# LISC_TopLevel.net
KiCad netlist of a schematic drawn in Altium Designer
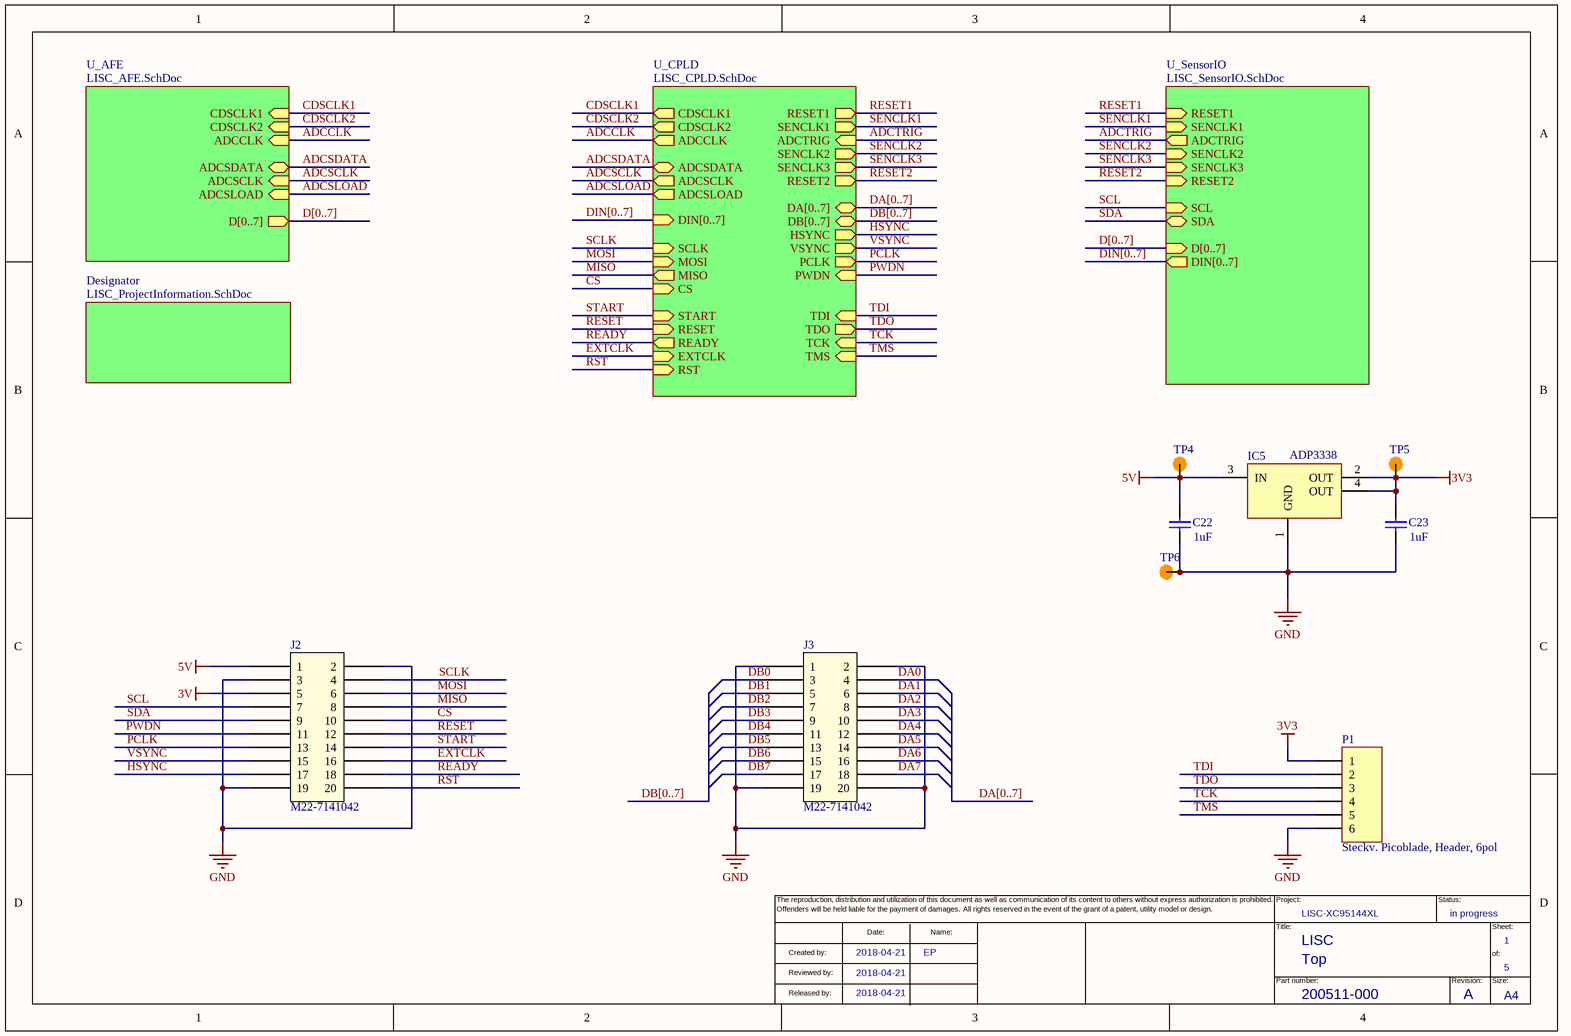
[diagram p0: LISC_TopLevel.SchDoc]

(export (version "E")
  (design (tool "Eeschema 10.0.6"))
  (components
    (comp (ref "C22")
      (value "1uF")
      (footprint "1608[0603]")
      (description "Capacitor (Semiconductor SIM Model)")
      (fields (field (name "PUBLISHER") "Altium Limited"))
      (libsource (lib "Miscellaneous Devices") (part "Cap Semi"))
    )
    (comp (ref "C23")
      (value "1uF")
      (footprint "1608[0603]")
      (description "Capacitor (Semiconductor SIM Model)")
      (fields (field (name "PUBLISHER") "Altium Limited"))
      (libsource (lib "Miscellaneous Devices") (part "Cap Semi"))
    )
    (comp (ref "IC5")
      (value "ADP3338")
      (footprint "SOT223-4L")
      (description "High Accuracy, Ultralow IQ, 1 A,  anyCAP® Low Dropout Regulator")
      (libsource (lib "V-REG_LT") (part "ADP3338"))
    )
    (comp (ref "J2")
      (value "M22-7141042")
      (footprint "PCBComponent_1")
      (description "Harwig M22-7141042")
      (libsource (lib "ConSpecial") (part "M22-7141042"))
    )
    (comp (ref "J3")
      (value "M22-7141042")
      (footprint "PCBComponent_1")
      (description "Harwig M22-7141042")
      (libsource (lib "ConSpecial") (part "M22-7141042"))
    )
    (comp (ref "P1")
      (value "Steckv. Picoblade, Header, 6pol")
      (footprint "PicoBlade Header 6Pin gerade")
      (description "MOLEX - 53047-0610 - STECKER,VERTIKAL,6KONT")
      (fields (field (name "MANUFACTURER") "MOLEX") (field (name "MANUFACTURER PART NUMBER") "53047-0610"))
      (libsource (lib "CON_MOLEX_LT") (part "1.25mm Pitch PicoBlade™ Wire-to-Board Header, Vertical, with Friction Lock, 6 Circuits"))
    )
    (comp (ref "TP4")
      (value "TP_SMD")
      (footprint "TP100_200_NS")
      (libsource (lib "LISC-XC95144XL") (part "TP_SMD"))
    )
    (comp (ref "TP5")
      (value "TP_SMD")
      (footprint "TP100_200_NS")
      (libsource (lib "LISC-XC95144XL") (part "TP_SMD"))
    )
    (comp (ref "TP6")
      (value "TP_SMD")
      (footprint "TP100_200_NS")
      (libsource (lib "LISC-XC95144XL") (part "TP_SMD"))
    )
  )
  (nets
    (net (code "24") (name "/CS") (class "Default")
      (node (ref "J2") (pin "10") (pinfunction "10_10") (pintype "passive"))
    )
    (net (code "25") (name "/DA0") (class "Default")
      (node (ref "J3") (pin "4") (pinfunction "4_4") (pintype "passive"))
    )
    (net (code "26") (name "/DA1") (class "Default")
      (node (ref "J3") (pin "6") (pinfunction "6_6") (pintype "passive"))
    )
    (net (code "27") (name "/DA2") (class "Default")
      (node (ref "J3") (pin "8") (pinfunction "8_8") (pintype "passive"))
    )
    (net (code "28") (name "/DA3") (class "Default")
      (node (ref "J3") (pin "10") (pinfunction "10_10") (pintype "passive"))
    )
    (net (code "29") (name "/DA4") (class "Default")
      (node (ref "J3") (pin "12") (pinfunction "12_12") (pintype "passive"))
    )
    (net (code "30") (name "/DA5") (class "Default")
      (node (ref "J3") (pin "14") (pinfunction "14_14") (pintype "passive"))
    )
    (net (code "31") (name "/DA6") (class "Default")
      (node (ref "J3") (pin "16") (pinfunction "16_16") (pintype "passive"))
    )
    (net (code "32") (name "/DA7") (class "Default")
      (node (ref "J3") (pin "18") (pinfunction "18_18") (pintype "passive"))
    )
    (net (code "34") (name "/DB0") (class "Default")
      (node (ref "J3") (pin "3") (pinfunction "3_3") (pintype "passive"))
    )
    (net (code "35") (name "/DB1") (class "Default")
      (node (ref "J3") (pin "5") (pinfunction "5_5") (pintype "passive"))
    )
    (net (code "36") (name "/DB2") (class "Default")
      (node (ref "J3") (pin "7") (pinfunction "7_7") (pintype "passive"))
    )
    (net (code "37") (name "/DB3") (class "Default")
      (node (ref "J3") (pin "9") (pinfunction "9_9") (pintype "passive"))
    )
    (net (code "38") (name "/DB4") (class "Default")
      (node (ref "J3") (pin "11") (pinfunction "11_11") (pintype "passive"))
    )
    (net (code "39") (name "/DB5") (class "Default")
      (node (ref "J3") (pin "13") (pinfunction "13_13") (pintype "passive"))
    )
    (net (code "40") (name "/DB6") (class "Default")
      (node (ref "J3") (pin "15") (pinfunction "15_15") (pintype "passive"))
    )
    (net (code "41") (name "/DB7") (class "Default")
      (node (ref "J3") (pin "17") (pinfunction "17_17") (pintype "passive"))
    )
    (net (code "45") (name "/EXTCLK") (class "Default")
      (node (ref "J2") (pin "16") (pinfunction "16_16") (pintype "passive"))
    )
    (net (code "46") (name "/HSYNC") (class "Default")
      (node (ref "J2") (pin "17") (pinfunction "17_17") (pintype "passive"))
    )
    (net (code "47") (name "/MISO") (class "Default")
      (node (ref "J2") (pin "8") (pinfunction "8_8") (pintype "passive"))
    )
    (net (code "48") (name "/MOSI") (class "Default")
      (node (ref "J2") (pin "6") (pinfunction "6_6") (pintype "passive"))
    )
    (net (code "49") (name "/PCLK") (class "Default")
      (node (ref "J2") (pin "13") (pinfunction "13_13") (pintype "passive"))
    )
    (net (code "50") (name "/PWDN") (class "Default")
      (node (ref "J2") (pin "11") (pinfunction "11_11") (pintype "passive"))
    )
    (net (code "51") (name "/READY") (class "Default")
      (node (ref "J2") (pin "18") (pinfunction "18_18") (pintype "passive"))
    )
    (net (code "52") (name "/RESET") (class "Default")
      (node (ref "J2") (pin "12") (pinfunction "12_12") (pintype "passive"))
    )
    (net (code "55") (name "/RST") (class "Default")
      (node (ref "J2") (pin "20") (pinfunction "20_20") (pintype "passive"))
    )
    (net (code "56") (name "/SCL") (class "Default")
      (node (ref "J2") (pin "7") (pinfunction "7_7") (pintype "passive"))
    )
    (net (code "57") (name "/SCLK") (class "Default")
      (node (ref "J2") (pin "4") (pinfunction "4_4") (pintype "passive"))
    )
    (net (code "58") (name "/SDA") (class "Default")
      (node (ref "J2") (pin "9") (pinfunction "9_9") (pintype "passive"))
    )
    (net (code "62") (name "/START") (class "Default")
      (node (ref "J2") (pin "14") (pinfunction "14_14") (pintype "passive"))
    )
    (net (code "63") (name "/TCK") (class "Default")
      (node (ref "P1") (pin "4") (pinfunction "4_4") (pintype "passive"))
    )
    (net (code "64") (name "/TDI") (class "Default")
      (node (ref "P1") (pin "2") (pinfunction "2_2") (pintype "passive"))
    )
    (net (code "65") (name "/TDO") (class "Default")
      (node (ref "P1") (pin "3") (pinfunction "3_3") (pintype "passive"))
    )
    (net (code "66") (name "/TMS") (class "Default")
      (node (ref "P1") (pin "5") (pinfunction "5_5") (pintype "passive"))
    )
    (net (code "67") (name "/VSYNC") (class "Default")
      (node (ref "J2") (pin "15") (pinfunction "15_15") (pintype "passive"))
    )
    (net (code "68") (name "3V") (class "Default")
      (node (ref "J2") (pin "5") (pinfunction "5_5") (pintype "passive"))
    )
    (net (code "69") (name "3V3") (class "Default")
      (node (ref "C23") (pin "2") (pinfunction "2_2") (pintype "passive"))
      (node (ref "IC5") (pin "2") (pinfunction "OUT_2") (pintype "power_in"))
      (node (ref "IC5") (pin "4") (pinfunction "OUT_4") (pintype "power_in"))
      (node (ref "P1") (pin "1") (pinfunction "1_1") (pintype "passive"))
      (node (ref "TP5") (pin "1") (pintype "passive"))
    )
    (net (code "70") (name "5V") (class "Default")
      (node (ref "C22") (pin "2") (pinfunction "2_2") (pintype "passive"))
      (node (ref "IC5") (pin "3") (pinfunction "IN_3") (pintype "power_in"))
      (node (ref "J2") (pin "1") (pinfunction "1_1") (pintype "passive"))
      (node (ref "TP4") (pin "1") (pintype "passive"))
    )
    (net (code "71") (name "GND") (class "Default")
      (node (ref "C22") (pin "1") (pinfunction "1_1") (pintype "passive"))
      (node (ref "C23") (pin "1") (pinfunction "1_1") (pintype "passive"))
      (node (ref "IC5") (pin "1") (pinfunction "GND_1") (pintype "power_in"))
      (node (ref "J2") (pin "19") (pinfunction "19_19") (pintype "passive"))
      (node (ref "J2") (pin "2") (pinfunction "2_2") (pintype "passive"))
      (node (ref "J2") (pin "3") (pinfunction "3_3") (pintype "passive"))
      (node (ref "J3") (pin "1") (pinfunction "1_1") (pintype "passive"))
      (node (ref "J3") (pin "19") (pinfunction "19_19") (pintype "passive"))
      (node (ref "J3") (pin "2") (pinfunction "2_2") (pintype "passive"))
      (node (ref "J3") (pin "20") (pinfunction "20_20") (pintype "passive"))
      (node (ref "P1") (pin "6") (pinfunction "6_6") (pintype "passive"))
      (node (ref "TP6") (pin "1") (pintype "passive"))
    )
  )
)
